# Misc.net
KiCad netlist of a schematic drawn in Altium Designer
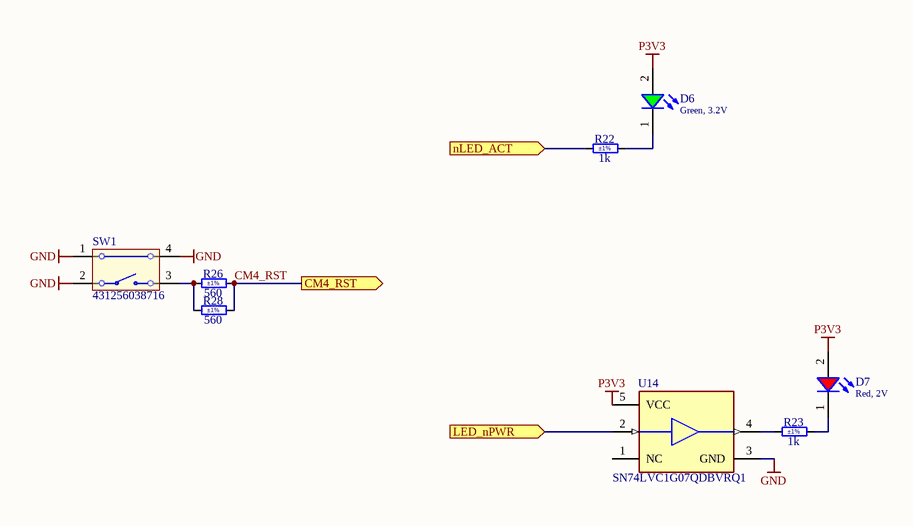
[diagram p0: Misc.SchDoc]

(export (version "E")
  (design (tool "Eeschema 10.0.6"))
  (components
    (comp (ref "D6")
      (value "Green, 3.2V")
      (footprint "WL-SMSW_0603_Rectangular")
      (description "WL-SMSW SMT Mono-color Side View Waterclear, size 0603, Green, 3.2V, 140deg")
      (fields
        (field (name "MANUFACTURER PART NUMBER") "155060GS75300")
        (field (name "MANUFACTURER") "Wurth Elektronik")
      )
      (libsource (lib "WL-SMSW (rev20b)") (part "155060GS75300"))
    )
    (comp (ref "D7")
      (value "Red, 2V")
      (footprint "WL-SMSW_0603_Rectangular")
      (description "WL-SMSW SMT Mono-color Side View Waterclear, size 0603, Red, 2V, 140deg")
      (fields
        (field (name "MANUFACTURER PART NUMBER") "155060RS75300")
        (field (name "MANUFACTURER") "Wurth Elektronik")
      )
      (libsource (lib "WL-SMSW (rev20b)") (part "155060RS75300"))
    )
    (comp (ref "R22")
      (value "1k")
      (footprint "RESC1005X40N")
      (description "Resistor - 1%")
      (fields
        (field (name "TOLERANCE") "±1%")
        (field (name "PART NUMBER") "R0402_1K_1%_0.0625W_100PPM")
        (field (name "POWER") "0.0625W")
        (field (name "AUTHOR") "CERN DEM JLC")
      )
      (libsource (lib "Resistors") (part "Resistor - 1%"))
    )
    (comp (ref "R23")
      (value "1k")
      (footprint "RESC1005X40N")
      (description "Resistor - 1%")
      (fields
        (field (name "TOLERANCE") "±1%")
        (field (name "PART NUMBER") "R0402_1K_1%_0.0625W_100PPM")
        (field (name "POWER") "0.0625W")
        (field (name "AUTHOR") "CERN DEM JLC")
      )
      (libsource (lib "Resistors") (part "Resistor - 1%"))
    )
    (comp (ref "R26")
      (value "560")
      (footprint "RESC1005X40N")
      (description "Resistor - 1%")
      (fields
        (field (name "TOLERANCE") "±1%")
        (field (name "PART NUMBER") "R0402_560R_1%_0.0625W_100PPM")
        (field (name "POWER") "0.0625W")
        (field (name "AUTHOR") "CERN DEM JLC")
      )
      (libsource (lib "Resistors") (part "Resistor - 1%"))
    )
    (comp (ref "R28")
      (value "560")
      (footprint "RESC1005X40N")
      (description "Resistor - 1%")
      (fields
        (field (name "TOLERANCE") "±1%")
        (field (name "PART NUMBER") "R0402_560R_1%_0.0625W_100PPM")
        (field (name "POWER") "0.0625W")
        (field (name "AUTHOR") "CERN DEM JLC")
      )
      (libsource (lib "Resistors") (part "Resistor - 1%"))
    )
    (comp (ref "SW1")
      (value "431256038716")
      (footprint "431256038716")
      (description "WS-TATU THT Tact Switch 6X6 mm right angle type with ground terminal")
      (fields (field (name "MANUFACTURER") "Wuerth Elektronik"))
      (libsource (lib "Altium Content Vault") (part "WE-TACT-SW-4_B"))
    )
    (comp (ref "U14")
      (value "SN74LVC1G07QDBVRQ1")
      (footprint "FP-DBV0005A-IPC_A")
      (description "IC BUF NON-INVERT 5.5V SOT23-5")
      (libsource (lib "Altium Content Vault") (part "fd2d5996bf727b2de8003b3fc962381"))
    )
  )
  (nets
    (net (code "1") (name "/CM4_RST") (class "Default")
      (node (ref "R26") (pin "2") (pinfunction "2_2") (pintype "passive"))
      (node (ref "R28") (pin "2") (pinfunction "2_2") (pintype "passive"))
    )
    (net (code "2") (name "/LED_nPWR") (class "Default")
      (node (ref "U14") (pin "2") (pinfunction "A_2") (pintype "input"))
    )
    (net (code "3") (name "/nLED_ACT") (class "Default")
      (node (ref "R22") (pin "1") (pinfunction "1_1") (pintype "passive"))
    )
    (net (code "4") (name "GND") (class "Default")
      (node (ref "SW1") (pin "1") (pinfunction "1_1") (pintype "passive"))
      (node (ref "SW1") (pin "2") (pinfunction "2_2") (pintype "passive"))
      (node (ref "SW1") (pin "4") (pinfunction "4_4") (pintype "passive"))
      (node (ref "U14") (pin "3") (pinfunction "GND_3") (pintype "power_in"))
    )
    (net (code "5") (name "Net-(D6-K)") (class "Default")
      (node (ref "D6") (pin "1") (pinfunction "K_1") (pintype "passive"))
      (node (ref "R22") (pin "2") (pinfunction "2_2") (pintype "passive"))
    )
    (net (code "6") (name "Net-(D7-K)") (class "Default")
      (node (ref "D7") (pin "1") (pinfunction "K_1") (pintype "passive"))
      (node (ref "R23") (pin "2") (pinfunction "2_2") (pintype "passive"))
    )
    (net (code "7") (name "Net-(R26-Pad1)") (class "Default")
      (node (ref "R26") (pin "1") (pinfunction "1_1") (pintype "passive"))
      (node (ref "R28") (pin "1") (pinfunction "1_1") (pintype "passive"))
      (node (ref "SW1") (pin "3") (pinfunction "3_3") (pintype "passive"))
    )
    (net (code "8") (name "Net-(U14-Y)") (class "Default")
      (node (ref "R23") (pin "1") (pinfunction "1_1") (pintype "passive"))
      (node (ref "U14") (pin "4") (pinfunction "Y_4") (pintype "output"))
    )
    (net (code "9") (name "P3V3") (class "Default")
      (node (ref "D6") (pin "2") (pinfunction "A_2") (pintype "passive"))
      (node (ref "D7") (pin "2") (pinfunction "A_2") (pintype "passive"))
      (node (ref "U14") (pin "5") (pinfunction "VCC_5") (pintype "power_in"))
    )
    (net (code "10") (name "unconnected-(U14-NC-Pad1)") (class "Default")
      (node (ref "U14") (pin "1") (pinfunction "NC_1") (pintype "passive"))
    )
  )
)
